# A.net
KiCad netlist of a schematic drawn in Altium Designer
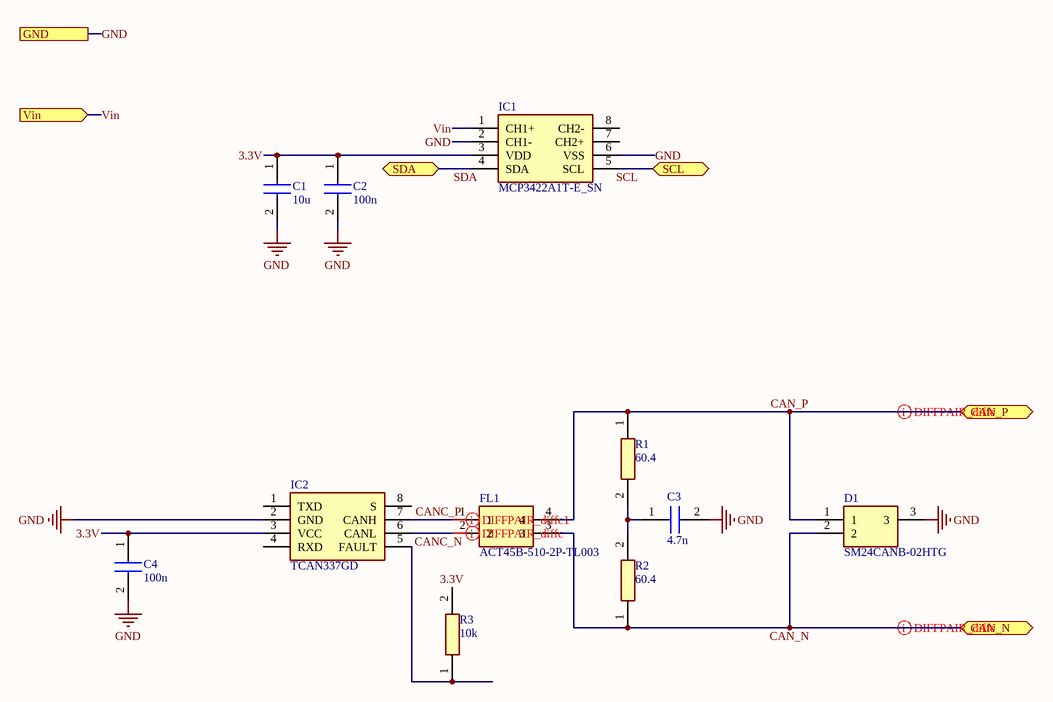
[diagram p0: A.SchDoc]

(export (version "E")
  (design (tool "Eeschema 10.0.6"))
  (components
    (comp (ref "C1")
      (value "10u")
      (footprint "CAPC1608X90N")
      (description "Capacitor")
      (fields (field (name "MANUFACTURER_PART_NUMBER") "CL10A106KQ8NNNL"))
      (libsource (lib "SamacSys") (part "CL10A106KQ8NNNL"))
    )
    (comp (ref "C2")
      (value "100n")
      (footprint "CAPC1608X90N")
      (description "Capacitor")
      (fields
        (field (name "MANUFACTURER_PART_NUMBER") "06035C104J4Z2A")
        (field (name "MOUSER PART NUMBER") "581-06035C104J4Z2A")
      )
      (libsource (lib "SamacSys") (part "06035C104J4Z2A"))
    )
    (comp (ref "C3")
      (value "4.7n")
      (footprint "CAPC1608X95N")
      (description "Capacitor")
      (fields (field (name "MANUFACTURER_PART_NUMBER") "0603B472M500CT"))
      (libsource (lib "SamacSys") (part "0603B472M500CT"))
    )
    (comp (ref "C4")
      (value "100n")
      (footprint "CAPC1608X90N")
      (description "Capacitor")
      (fields
        (field (name "MANUFACTURER_PART_NUMBER") "06035C104J4Z2A")
        (field (name "MOUSER PART NUMBER") "581-06035C104J4Z2A")
      )
      (libsource (lib "SamacSys") (part "06035C104J4Z2A"))
    )
    (comp (ref "D1")
      (value "SM24CANB-02HTG")
      (footprint "SM24CANB02HTG")
      (description "TVS Diode (Bi-directional)")
      (fields (field (name "MOUSER PART NUMBER") "576-SM24CANB-02HTG"))
      (libsource (lib "SamacSys") (part "SM24CANB-02HTG"))
    )
    (comp (ref "FL1")
      (value "ACT45B-510-2P-TL003")
      (footprint "ACT45B1012PTL003")
      (description "Filter")
      (fields (field (name "MOUSER PART NUMBER") "810-ACT45B5102PTL003"))
      (libsource (lib "SamacSys") (part "ACT45B-510-2P-TL003"))
    )
    (comp (ref "IC1")
      (value "MCP3422A1T-E_SN")
      (footprint "SOIC127P600X175-8N")
      (description "Integrated Circuit")
      (fields
        (field (name "MANUFACTURER_PART_NUMBER") "MCP3422A1T-E/SN")
        (field (name "MOUSER PART NUMBER") "579-MCP3422A1T-E/SN")
      )
      (libsource (lib "SamacSys") (part "MCP3422A1T-E_SN"))
    )
    (comp (ref "IC2")
      (value "TCAN337GD")
      (footprint "SOIC127P600X175-8N")
      (description "Integrated Circuit")
      (fields (field (name "MOUSER PART NUMBER") "595-TCAN337GD"))
      (libsource (lib "SamacSys") (part "TCAN337GD"))
    )
    (comp (ref "R1")
      (value "60.4")
      (footprint "RESC1608X50N")
      (description "Resistor")
      (fields
        (field (name "MANUFACTURER_PART_NUMBER") "CRCW060360R4FKEA")
        (field (name "MOUSER PART NUMBER") "71-CRCW0603-60.4-E3")
      )
      (libsource (lib "SamacSys") (part "CRCW060360R4FKEA"))
    )
    (comp (ref "R2")
      (value "60.4")
      (footprint "RESC1608X50N")
      (description "Resistor")
      (fields
        (field (name "MANUFACTURER_PART_NUMBER") "CRCW060360R4FKEA")
        (field (name "MOUSER PART NUMBER") "71-CRCW0603-60.4-E3")
      )
      (libsource (lib "") (part "CRCW060360R4FKEA_1"))
    )
    (comp (ref "R3")
      (value "10k")
      (footprint "RESC1608X55N")
      (description "Resistor")
      (fields
        (field (name "MANUFACTURER_PART_NUMBER") "CRGCQ0603F10K")
        (field (name "MOUSER PART NUMBER") "279-CRGCQ0603F10K")
      )
      (libsource (lib "SamacSys") (part "CRGCQ0603F10K"))
    )
  )
  (nets
    (net (code "1") (name "/3.3V") (class "Default")
      (node (ref "C1") (pin "1") (pinfunction "1_1") (pintype "passive"))
      (node (ref "C2") (pin "1") (pinfunction "1_1") (pintype "passive"))
      (node (ref "C4") (pin "1") (pinfunction "1_1") (pintype "passive"))
      (node (ref "IC1") (pin "3") (pinfunction "VDD_3") (pintype "passive"))
      (node (ref "IC2") (pin "3") (pinfunction "VCC_3") (pintype "passive"))
      (node (ref "R3") (pin "2") (pinfunction "2_2") (pintype "passive"))
    )
    (net (code "2") (name "/CANC_N") (class "Default")
      (node (ref "FL1") (pin "2") (pinfunction "2_2") (pintype "passive"))
      (node (ref "IC2") (pin "6") (pinfunction "CANL_6") (pintype "passive"))
    )
    (net (code "3") (name "/CANC_P") (class "Default")
      (node (ref "FL1") (pin "1") (pinfunction "1_1") (pintype "passive"))
      (node (ref "IC2") (pin "7") (pinfunction "CANH_7") (pintype "passive"))
    )
    (net (code "4") (name "/CAN_N") (class "Default")
      (node (ref "D1") (pin "2") (pinfunction "2_2") (pintype "passive"))
      (node (ref "FL1") (pin "3") (pinfunction "3_3") (pintype "passive"))
      (node (ref "R2") (pin "1") (pinfunction "1_1") (pintype "passive"))
    )
    (net (code "5") (name "/CAN_P") (class "Default")
      (node (ref "D1") (pin "1") (pinfunction "1_1") (pintype "passive"))
      (node (ref "FL1") (pin "4") (pinfunction "4_4") (pintype "passive"))
      (node (ref "R1") (pin "1") (pinfunction "1_1") (pintype "passive"))
    )
    (net (code "6") (name "/SCL") (class "Default")
      (node (ref "IC1") (pin "5") (pinfunction "SCL_5") (pintype "passive"))
    )
    (net (code "7") (name "/SDA") (class "Default")
      (node (ref "IC1") (pin "4") (pinfunction "SDA_4") (pintype "passive"))
    )
    (net (code "8") (name "/Vin") (class "Default")
      (node (ref "IC1") (pin "1") (pinfunction "CH1+_1") (pintype "passive"))
    )
    (net (code "9") (name "GND") (class "Default")
      (node (ref "C1") (pin "2") (pinfunction "2_2") (pintype "passive"))
      (node (ref "C2") (pin "2") (pinfunction "2_2") (pintype "passive"))
      (node (ref "C3") (pin "2") (pinfunction "2_2") (pintype "passive"))
      (node (ref "C4") (pin "2") (pinfunction "2_2") (pintype "passive"))
      (node (ref "D1") (pin "3") (pinfunction "3_3") (pintype "passive"))
      (node (ref "IC1") (pin "2") (pinfunction "CH1-_2") (pintype "passive"))
      (node (ref "IC1") (pin "6") (pinfunction "VSS_6") (pintype "passive"))
      (node (ref "IC2") (pin "2") (pinfunction "GND_2") (pintype "passive"))
    )
    (net (code "10") (name "Net-(C3-Pad1)") (class "Default")
      (node (ref "C3") (pin "1") (pinfunction "1_1") (pintype "passive"))
      (node (ref "R1") (pin "2") (pinfunction "2_2") (pintype "passive"))
      (node (ref "R2") (pin "2") (pinfunction "2_2") (pintype "passive"))
    )
    (net (code "11") (name "Net-(IC2-FAULT)") (class "Default")
      (node (ref "IC2") (pin "5") (pinfunction "FAULT_5") (pintype "passive"))
      (node (ref "R3") (pin "1") (pinfunction "1_1") (pintype "passive"))
    )
    (net (code "12") (name "unconnected-(IC1-CH2+-Pad7)") (class "Default")
      (node (ref "IC1") (pin "7") (pinfunction "CH2+_7") (pintype "passive"))
    )
    (net (code "13") (name "unconnected-(IC1-CH2--Pad8)") (class "Default")
      (node (ref "IC1") (pin "8") (pinfunction "CH2-_8") (pintype "passive"))
    )
    (net (code "14") (name "unconnected-(IC2-RXD-Pad4)") (class "Default")
      (node (ref "IC2") (pin "4") (pinfunction "RXD_4") (pintype "passive"))
    )
    (net (code "15") (name "unconnected-(IC2-S-Pad8)") (class "Default")
      (node (ref "IC2") (pin "8") (pinfunction "S_8") (pintype "passive"))
    )
    (net (code "16") (name "unconnected-(IC2-TXD-Pad1)") (class "Default")
      (node (ref "IC2") (pin "1") (pinfunction "TXD_1") (pintype "passive"))
    )
  )
)
